# battiny_power_module.net
KiCad netlist of a schematic drawn in EAGLE
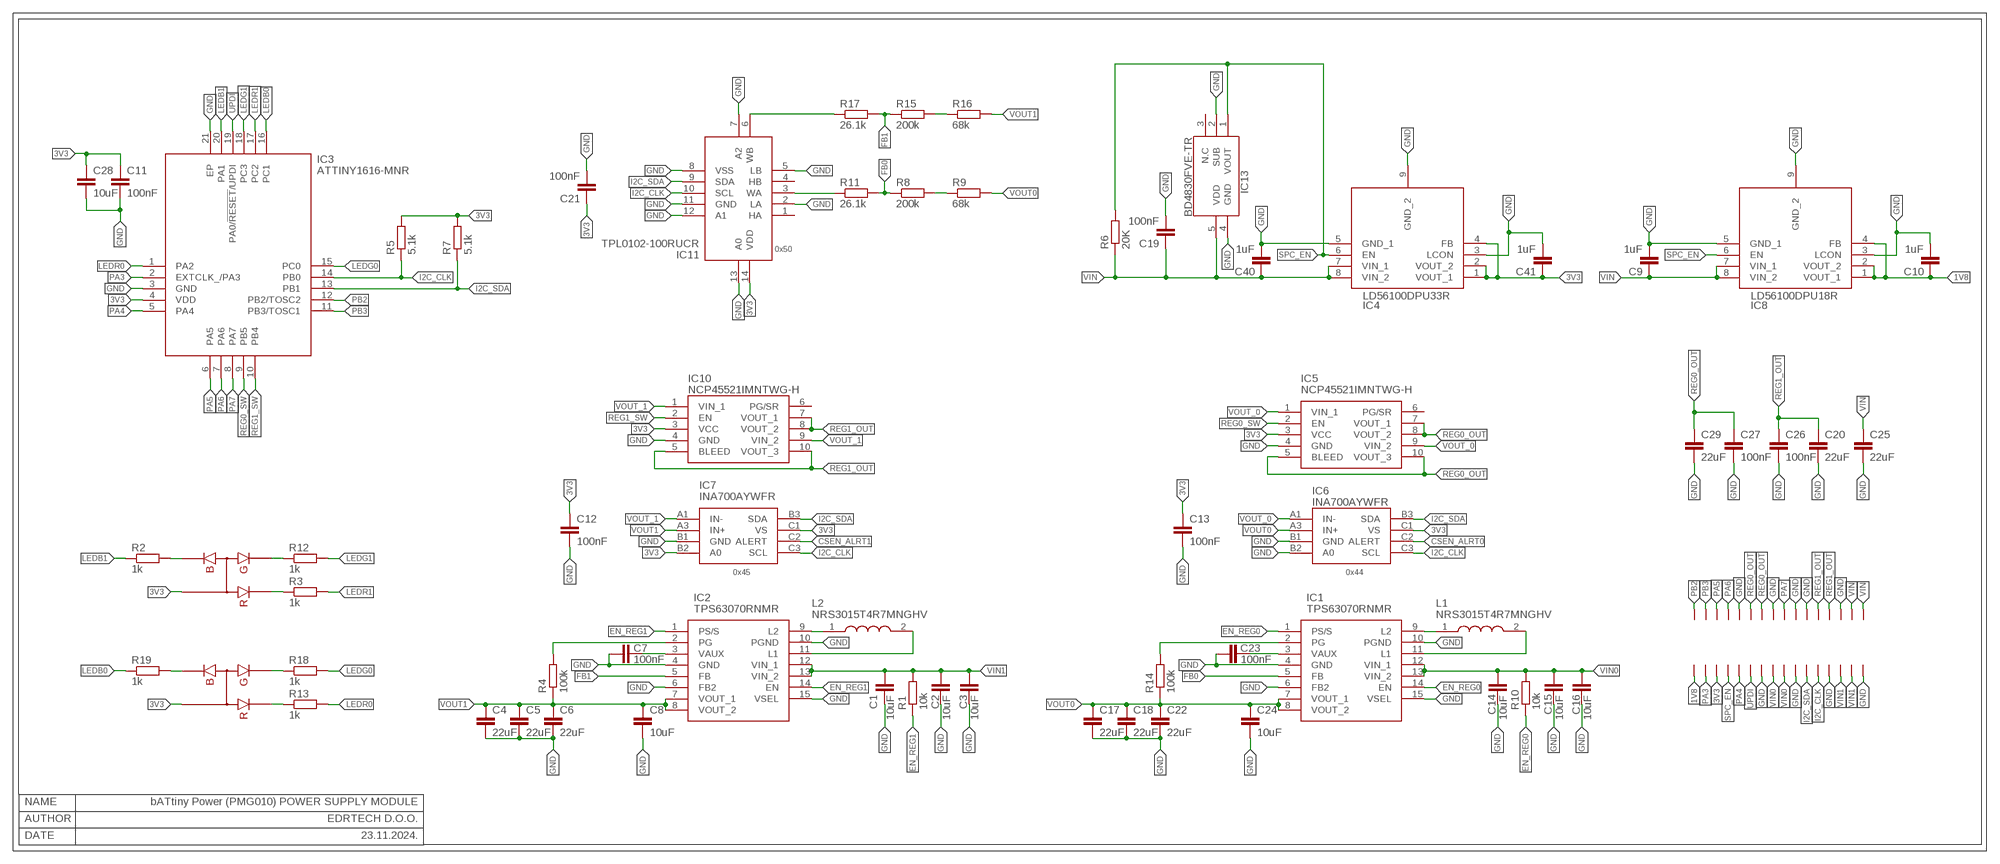
[diagram p0: schematic, sheet 1]

(export (version "E")
  (design (tool "Eeschema 10.0.6"))
  (components
    (comp (ref "C1")
      (value "10uF")
      (footprint "eagle-import:C0402")
      (libsource (lib "eagle-import") (part "C-EUC0402"))
    )
    (comp (ref "C2")
      (value "10uF")
      (footprint "eagle-import:C0402")
      (libsource (lib "eagle-import") (part "C-EUC0402"))
    )
    (comp (ref "C3")
      (value "10uF")
      (footprint "eagle-import:C0402")
      (libsource (lib "eagle-import") (part "C-EUC0402"))
    )
    (comp (ref "C4")
      (value "22uF")
      (footprint "eagle-import:C0603")
      (libsource (lib "eagle-import") (part "C-EUC0603"))
    )
    (comp (ref "C5")
      (value "22uF")
      (footprint "eagle-import:C0603")
      (libsource (lib "eagle-import") (part "C-EUC0603"))
    )
    (comp (ref "C6")
      (value "22uF")
      (footprint "eagle-import:C0603")
      (libsource (lib "eagle-import") (part "C-EUC0603"))
    )
    (comp (ref "C7")
      (value "100nF")
      (footprint "eagle-import:HPC0201")
      (libsource (lib "eagle-import") (part "C-EUHPC0201"))
    )
    (comp (ref "C8")
      (value "10uF")
      (footprint "eagle-import:C0402")
      (libsource (lib "eagle-import") (part "C-EUC0402"))
    )
    (comp (ref "C9")
      (value "1uF")
      (footprint "eagle-import:C0201")
      (libsource (lib "eagle-import") (part "C-EUC0201"))
    )
    (comp (ref "C10")
      (value "1uF")
      (footprint "eagle-import:C0201")
      (libsource (lib "eagle-import") (part "C-EUC0201"))
    )
    (comp (ref "C11")
      (value "100nF")
      (footprint "eagle-import:C0201")
      (libsource (lib "eagle-import") (part "C-EUC0201"))
    )
    (comp (ref "C12")
      (value "100nF")
      (footprint "eagle-import:C0201")
      (libsource (lib "eagle-import") (part "C-EUC0201"))
    )
    (comp (ref "C13")
      (value "100nF")
      (footprint "eagle-import:C0201")
      (libsource (lib "eagle-import") (part "C-EUC0201"))
    )
    (comp (ref "C14")
      (value "10uF")
      (footprint "eagle-import:C0402")
      (libsource (lib "eagle-import") (part "C-EUC0402"))
    )
    (comp (ref "C15")
      (value "10uF")
      (footprint "eagle-import:C0402")
      (libsource (lib "eagle-import") (part "C-EUC0402"))
    )
    (comp (ref "C16")
      (value "10uF")
      (footprint "eagle-import:C0402")
      (libsource (lib "eagle-import") (part "C-EUC0402"))
    )
    (comp (ref "C17")
      (value "22uF")
      (footprint "eagle-import:C0603")
      (libsource (lib "eagle-import") (part "C-EUC0603"))
    )
    (comp (ref "C18")
      (value "22uF")
      (footprint "eagle-import:C0603")
      (libsource (lib "eagle-import") (part "C-EUC0603"))
    )
    (comp (ref "C19")
      (value "100nF")
      (footprint "eagle-import:C0201")
      (libsource (lib "eagle-import") (part "C-EUC0201"))
    )
    (comp (ref "C20")
      (value "22uF")
      (footprint "eagle-import:C0805K")
      (libsource (lib "eagle-import") (part "C-EUC0805K"))
    )
    (comp (ref "C21")
      (value "100nF")
      (footprint "eagle-import:C0201")
      (libsource (lib "eagle-import") (part "C-EUC0201"))
    )
    (comp (ref "C22")
      (value "22uF")
      (footprint "eagle-import:C0603")
      (libsource (lib "eagle-import") (part "C-EUC0603"))
    )
    (comp (ref "C23")
      (value "100nF")
      (footprint "eagle-import:HPC0201")
      (libsource (lib "eagle-import") (part "C-EUHPC0201"))
    )
    (comp (ref "C24")
      (value "10uF")
      (footprint "eagle-import:C0402")
      (libsource (lib "eagle-import") (part "C-EUC0402"))
    )
    (comp (ref "C25")
      (value "22uF")
      (footprint "eagle-import:C0805K")
      (libsource (lib "eagle-import") (part "C-EUC0805K"))
    )
    (comp (ref "C26")
      (value "100nF")
      (footprint "eagle-import:C0603")
      (libsource (lib "eagle-import") (part "C-EUC0603"))
    )
    (comp (ref "C27")
      (value "100nF")
      (footprint "eagle-import:C0603")
      (libsource (lib "eagle-import") (part "C-EUC0603"))
    )
    (comp (ref "C28")
      (value "10uF")
      (footprint "eagle-import:C0402")
      (libsource (lib "eagle-import") (part "C-EUC0402"))
    )
    (comp (ref "C29")
      (value "22uF")
      (footprint "eagle-import:C0805K")
      (libsource (lib "eagle-import") (part "C-EUC0805K"))
    )
    (comp (ref "C40")
      (value "1uF")
      (footprint "eagle-import:C0201")
      (libsource (lib "eagle-import") (part "C-EUC0201"))
    )
    (comp (ref "C41")
      (value "1uF")
      (footprint "eagle-import:C0201")
      (libsource (lib "eagle-import") (part "C-EUC0201"))
    )
    (comp (ref "IC1")
      (value "TPS63070RNMR")
      (footprint "eagle-import:TPS630701RNMR")
      (fields (field (name "MOUSER_PART_NUMBER") "595-TPS63070RNMR"))
      (libsource (lib "eagle-import") (part "TPS63070RNMR"))
    )
    (comp (ref "IC2")
      (value "TPS63070RNMR")
      (footprint "eagle-import:TPS630701RNMR")
      (fields (field (name "MOUSER_PART_NUMBER") "595-TPS63070RNMR"))
      (libsource (lib "eagle-import") (part "TPS63070RNMR"))
    )
    (comp (ref "IC3")
      (value "ATTINY1616-MNR")
      (footprint "eagle-import:QFN40P300X300X90-21N")
      (fields (field (name "MOUSER_PART_NUMBER") "556-ATTINY1616MNR"))
      (libsource (lib "eagle-import") (part "ATTINY1616-MNR"))
    )
    (comp (ref "IC4")
      (value "LD56100DPU30R")
      (footprint "eagle-import:SON40P120X160X50-9N")
      (fields (field (name "MOUSER_PART_NUMBER") "511-LD56100DPU30R"))
      (libsource (lib "eagle-import") (part "LD56100DPU30R"))
    )
    (comp (ref "IC5")
      (value "NCP45521IMNTWG-H")
      (footprint "eagle-import:NCP45521")
      (fields (field (name "MOUSER_PART_NUMBER") "863-NCP45521IMNTWG-H"))
      (libsource (lib "eagle-import") (part "NCP45521IMNTWG-H"))
    )
    (comp (ref "IC6")
      (value "INA700AYWFR")
      (footprint "eagle-import:INA700AYWFR")
      (libsource (lib "eagle-import") (part "INA700AYWFR"))
    )
    (comp (ref "IC7")
      (value "INA700AYWFR")
      (footprint "eagle-import:INA700AYWFR")
      (libsource (lib "eagle-import") (part "INA700AYWFR"))
    )
    (comp (ref "IC8")
      (value "LD56100DPU30R")
      (footprint "eagle-import:SON40P120X160X50-9N")
      (fields (field (name "MOUSER_PART_NUMBER") "511-LD56100DPU30R"))
      (libsource (lib "eagle-import") (part "LD56100DPU30R"))
    )
    (comp (ref "IC10")
      (value "NCP45521IMNTWG-H")
      (footprint "eagle-import:NCP45521")
      (fields (field (name "MOUSER_PART_NUMBER") "863-NCP45521IMNTWG-H"))
      (libsource (lib "eagle-import") (part "NCP45521IMNTWG-H"))
    )
    (comp (ref "IC11")
      (value "TPL0102-100RUCR")
      (footprint "eagle-import:QFN40P200X200X40-14N")
      (libsource (lib "eagle-import") (part "TPL0102-100RUCR"))
    )
    (comp (ref "IC13")
      (value "BD4830FVE-TR")
      (footprint "eagle-import:SOTFL50P160X60-5N")
      (fields (field (name "MOUSER_PART_NUMBER") "755-BD4830FVE-TR"))
      (libsource (lib "eagle-import") (part "BD4830FVE-TR"))
    )
    (comp (ref "L1")
      (value "NRS3015T4R7MNGHV")
      (footprint "eagle-import:NRS3015T4R7MNGHV")
      (fields (field (name "MOUSER_PART_NUMBER") "963-NRS3015T4R7MNGHV"))
      (libsource (lib "eagle-import") (part "NRS3015T4R7MNGHV"))
    )
    (comp (ref "L2")
      (value "NRS3015T4R7MNGHV")
      (footprint "eagle-import:NRS3015T4R7MNGHV")
      (fields (field (name "MOUSER_PART_NUMBER") "963-NRS3015T4R7MNGHV"))
      (libsource (lib "eagle-import") (part "NRS3015T4R7MNGHV"))
    )
    (comp (ref "R1")
      (value "10k")
      (footprint "eagle-import:R0201")
      (libsource (lib "eagle-import") (part "R-EU_R0201"))
    )
    (comp (ref "R2")
      (value "1k")
      (footprint "eagle-import:R0201")
      (libsource (lib "eagle-import") (part "R-EU_R0201"))
    )
    (comp (ref "R3")
      (value "1k")
      (footprint "eagle-import:R0201")
      (libsource (lib "eagle-import") (part "R-EU_R0201"))
    )
    (comp (ref "R4")
      (value "100k")
      (footprint "eagle-import:R0201")
      (libsource (lib "eagle-import") (part "R-EU_R0201"))
    )
    (comp (ref "R5")
      (value "5.1k")
      (footprint "eagle-import:R0201")
      (libsource (lib "eagle-import") (part "R-EU_R0201"))
    )
    (comp (ref "R6")
      (value "20K")
      (footprint "eagle-import:R0201")
      (libsource (lib "eagle-import") (part "R-EU_R0201"))
    )
    (comp (ref "R7")
      (value "5.1k")
      (footprint "eagle-import:R0201")
      (libsource (lib "eagle-import") (part "R-EU_R0201"))
    )
    (comp (ref "R8")
      (value "200k")
      (footprint "eagle-import:R0201")
      (libsource (lib "eagle-import") (part "R-EU_R0201"))
    )
    (comp (ref "R9")
      (value "68k")
      (footprint "eagle-import:R0201")
      (libsource (lib "eagle-import") (part "R-EU_R0201"))
    )
    (comp (ref "R10")
      (value "10k")
      (footprint "eagle-import:R0201")
      (libsource (lib "eagle-import") (part "R-EU_R0201"))
    )
    (comp (ref "R11")
      (value "26.1k")
      (footprint "eagle-import:R0201")
      (libsource (lib "eagle-import") (part "R-EU_R0201"))
    )
    (comp (ref "R12")
      (value "1k")
      (footprint "eagle-import:R0201")
      (libsource (lib "eagle-import") (part "R-EU_R0201"))
    )
    (comp (ref "R13")
      (value "1k")
      (footprint "eagle-import:R0201")
      (libsource (lib "eagle-import") (part "R-EU_R0201"))
    )
    (comp (ref "R14")
      (value "100k")
      (footprint "eagle-import:R0201")
      (libsource (lib "eagle-import") (part "R-EU_R0201"))
    )
    (comp (ref "R15")
      (value "200k")
      (footprint "eagle-import:R0201")
      (libsource (lib "eagle-import") (part "R-EU_R0201"))
    )
    (comp (ref "R16")
      (value "68k")
      (footprint "eagle-import:R0201")
      (libsource (lib "eagle-import") (part "R-EU_R0201"))
    )
    (comp (ref "R17")
      (value "26.1k")
      (footprint "eagle-import:R0201")
      (libsource (lib "eagle-import") (part "R-EU_R0201"))
    )
    (comp (ref "R18")
      (value "1k")
      (footprint "eagle-import:R0201")
      (libsource (lib "eagle-import") (part "R-EU_R0201"))
    )
    (comp (ref "R19")
      (value "1k")
      (footprint "eagle-import:R0201")
      (libsource (lib "eagle-import") (part "R-EU_R0201"))
    )
    (comp (ref "U$1")
      (value "1.27_CH_16P")
      (footprint "eagle-import:1.27_CH_16P")
      (libsource (lib "eagle-import") (part "1.27_CH_16P"))
    )
    (comp (ref "U$2")
      (value "1.27_CH_16P")
      (footprint "eagle-import:1.27_CH_16P")
      (libsource (lib "eagle-import") (part "1.27_CH_16P"))
    )
    (comp (ref "U$3")
      (value "XL-B1010RGBT-HF")
      (footprint "eagle-import:TBA-C1010MB-J2I16")
      (libsource (lib "eagle-import") (part "XL-B1010RGBT-HF"))
    )
    (comp (ref "U$4")
      (value "XL-B1010RGBT-HF")
      (footprint "eagle-import:TBA-C1010MB-J2I16")
      (libsource (lib "eagle-import") (part "XL-B1010RGBT-HF"))
    )
  )
  (nets
    (net (code "1") (name "1V8") (class "Default")
      (node (ref "C10") (pin "1") (pinfunction "1_1") (pintype "passive"))
      (node (ref "IC8") (pin "1") (pinfunction "VOUT_1_1") (pintype "bidirectional"))
      (node (ref "IC8") (pin "2") (pinfunction "VOUT_2_2") (pintype "bidirectional"))
      (node (ref "IC8") (pin "4") (pinfunction "FB_4") (pintype "bidirectional"))
      (node (ref "U$2") (pin "P$32") (pinfunction "P$16_P$32") (pintype "bidirectional"))
      (node (ref "U$2") (pin "P$48") (pinfunction "P$16_P$48") (pintype "bidirectional"))
    )
    (net (code "2") (name "3V3") (class "Default")
      (node (ref "C11") (pin "1") (pinfunction "1_1") (pintype "passive"))
      (node (ref "C12") (pin "1") (pinfunction "1_1") (pintype "passive"))
      (node (ref "C13") (pin "1") (pinfunction "1_1") (pintype "passive"))
      (node (ref "C21") (pin "1") (pinfunction "1_1") (pintype "passive"))
      (node (ref "C28") (pin "1") (pinfunction "1_1") (pintype "passive"))
      (node (ref "C41") (pin "1") (pinfunction "1_1") (pintype "passive"))
      (node (ref "IC10") (pin "3") (pinfunction "VCC_3") (pintype "bidirectional"))
      (node (ref "IC11") (pin "14") (pinfunction "VDD_14") (pintype "bidirectional"))
      (node (ref "IC3") (pin "4") (pinfunction "VDD_4") (pintype "bidirectional"))
      (node (ref "IC4") (pin "1") (pinfunction "VOUT_1_1") (pintype "bidirectional"))
      (node (ref "IC4") (pin "2") (pinfunction "VOUT_2_2") (pintype "bidirectional"))
      (node (ref "IC4") (pin "4") (pinfunction "FB_4") (pintype "bidirectional"))
      (node (ref "IC5") (pin "3") (pinfunction "VCC_3") (pintype "bidirectional"))
      (node (ref "IC6") (pin "C1") (pinfunction "VS_C1") (pintype "bidirectional"))
      (node (ref "IC7") (pin "B2") (pinfunction "A0_B2") (pintype "bidirectional"))
      (node (ref "IC7") (pin "C1") (pinfunction "VS_C1") (pintype "bidirectional"))
      (node (ref "R5") (pin "2") (pinfunction "2_2") (pintype "passive"))
      (node (ref "R7") (pin "2") (pinfunction "2_2") (pintype "passive"))
      (node (ref "U$2") (pin "P$30") (pinfunction "P$14_P$30") (pintype "bidirectional"))
      (node (ref "U$2") (pin "P$46") (pinfunction "P$14_P$46") (pintype "bidirectional"))
      (node (ref "U$3") (pin "P$3") (pinfunction "P$2_P$3") (pintype "bidirectional"))
      (node (ref "U$4") (pin "P$3") (pinfunction "P$2_P$3") (pintype "bidirectional"))
    )
    (net (code "3") (name "CSEN_ALRT0") (class "Default")
      (node (ref "IC6") (pin "C2") (pinfunction "ALERT_C2") (pintype "bidirectional"))
    )
    (net (code "4") (name "CSEN_ALRT1") (class "Default")
      (node (ref "IC7") (pin "C2") (pinfunction "ALERT_C2") (pintype "bidirectional"))
    )
    (net (code "5") (name "EN_REG0") (class "Default")
      (node (ref "IC1") (pin "1") (pinfunction "PS/S_1") (pintype "bidirectional"))
      (node (ref "IC1") (pin "14") (pinfunction "EN_14") (pintype "bidirectional"))
      (node (ref "R10") (pin "1") (pinfunction "1_1") (pintype "passive"))
    )
    (net (code "6") (name "EN_REG1") (class "Default")
      (node (ref "IC2") (pin "1") (pinfunction "PS/S_1") (pintype "bidirectional"))
      (node (ref "IC2") (pin "14") (pinfunction "EN_14") (pintype "bidirectional"))
      (node (ref "R1") (pin "1") (pinfunction "1_1") (pintype "passive"))
    )
    (net (code "7") (name "FB0") (class "Default")
      (node (ref "IC1") (pin "5") (pinfunction "FB_5") (pintype "bidirectional"))
      (node (ref "R11") (pin "2") (pinfunction "2_2") (pintype "passive"))
      (node (ref "R8") (pin "1") (pinfunction "1_1") (pintype "passive"))
    )
    (net (code "8") (name "FB1") (class "Default")
      (node (ref "IC2") (pin "5") (pinfunction "FB_5") (pintype "bidirectional"))
      (node (ref "R15") (pin "1") (pinfunction "1_1") (pintype "passive"))
      (node (ref "R17") (pin "2") (pinfunction "2_2") (pintype "passive"))
    )
    (net (code "9") (name "GND") (class "Default")
      (node (ref "C1") (pin "2") (pinfunction "2_2") (pintype "passive"))
      (node (ref "C10") (pin "2") (pinfunction "2_2") (pintype "passive"))
      (node (ref "C11") (pin "2") (pinfunction "2_2") (pintype "passive"))
      (node (ref "C12") (pin "2") (pinfunction "2_2") (pintype "passive"))
      (node (ref "C13") (pin "2") (pinfunction "2_2") (pintype "passive"))
      (node (ref "C14") (pin "2") (pinfunction "2_2") (pintype "passive"))
      (node (ref "C15") (pin "2") (pinfunction "2_2") (pintype "passive"))
      (node (ref "C16") (pin "2") (pinfunction "2_2") (pintype "passive"))
      (node (ref "C17") (pin "2") (pinfunction "2_2") (pintype "passive"))
      (node (ref "C18") (pin "2") (pinfunction "2_2") (pintype "passive"))
      (node (ref "C19") (pin "2") (pinfunction "2_2") (pintype "passive"))
      (node (ref "C2") (pin "2") (pinfunction "2_2") (pintype "passive"))
      (node (ref "C20") (pin "2") (pinfunction "2_2") (pintype "passive"))
      (node (ref "C21") (pin "2") (pinfunction "2_2") (pintype "passive"))
      (node (ref "C22") (pin "2") (pinfunction "2_2") (pintype "passive"))
      (node (ref "C23") (pin "1") (pinfunction "1_1") (pintype "passive"))
      (node (ref "C24") (pin "2") (pinfunction "2_2") (pintype "passive"))
      (node (ref "C25") (pin "2") (pinfunction "2_2") (pintype "passive"))
      (node (ref "C26") (pin "2") (pinfunction "2_2") (pintype "passive"))
      (node (ref "C27") (pin "2") (pinfunction "2_2") (pintype "passive"))
      (node (ref "C28") (pin "2") (pinfunction "2_2") (pintype "passive"))
      (node (ref "C29") (pin "2") (pinfunction "2_2") (pintype "passive"))
      (node (ref "C3") (pin "2") (pinfunction "2_2") (pintype "passive"))
      (node (ref "C4") (pin "2") (pinfunction "2_2") (pintype "passive"))
      (node (ref "C40") (pin "2") (pinfunction "2_2") (pintype "passive"))
      (node (ref "C41") (pin "2") (pinfunction "2_2") (pintype "passive"))
      (node (ref "C5") (pin "2") (pinfunction "2_2") (pintype "passive"))
      (node (ref "C6") (pin "2") (pinfunction "2_2") (pintype "passive"))
      (node (ref "C7") (pin "1") (pinfunction "1_1") (pintype "passive"))
      (node (ref "C8") (pin "2") (pinfunction "2_2") (pintype "passive"))
      (node (ref "C9") (pin "2") (pinfunction "2_2") (pintype "passive"))
      (node (ref "IC1") (pin "10") (pinfunction "PGND_10") (pintype "bidirectional"))
      (node (ref "IC1") (pin "15") (pinfunction "VSEL_15") (pintype "bidirectional"))
      (node (ref "IC1") (pin "4") (pinfunction "GND_4") (pintype "bidirectional"))
      (node (ref "IC1") (pin "6") (pinfunction "FB2_6") (pintype "bidirectional"))
      (node (ref "IC10") (pin "4") (pinfunction "GND_4") (pintype "bidirectional"))
      (node (ref "IC11") (pin "11") (pinfunction "GND_11") (pintype "bidirectional"))
      (node (ref "IC11") (pin "12") (pinfunction "A1_12") (pintype "bidirectional"))
      (node (ref "IC11") (pin "13") (pinfunction "A0_13") (pintype "bidirectional"))
      (node (ref "IC11") (pin "2") (pinfunction "LA_2") (pintype "bidirectional"))
      (node (ref "IC11") (pin "5") (pinfunction "LB_5") (pintype "bidirectional"))
      (node (ref "IC11") (pin "7") (pinfunction "A2_7") (pintype "bidirectional"))
      (node (ref "IC11") (pin "8") (pinfunction "VSS_8") (pintype "bidirectional"))
      (node (ref "IC13") (pin "2") (pinfunction "SUB_2") (pintype "bidirectional"))
      (node (ref "IC13") (pin "4") (pinfunction "GND_4") (pintype "bidirectional"))
      (node (ref "IC2") (pin "10") (pinfunction "PGND_10") (pintype "bidirectional"))
      (node (ref "IC2") (pin "15") (pinfunction "VSEL_15") (pintype "bidirectional"))
      (node (ref "IC2") (pin "4") (pinfunction "GND_4") (pintype "bidirectional"))
      (node (ref "IC2") (pin "6") (pinfunction "FB2_6") (pintype "bidirectional"))
      (node (ref "IC3") (pin "21") (pinfunction "EP_21") (pintype "bidirectional"))
      (node (ref "IC3") (pin "3") (pinfunction "GND_3") (pintype "bidirectional"))
      (node (ref "IC4") (pin "3") (pinfunction "LCON_3") (pintype "bidirectional"))
      (node (ref "IC4") (pin "5") (pinfunction "GND_1_5") (pintype "bidirectional"))
      (node (ref "IC4") (pin "9") (pinfunction "GND_2_9") (pintype "bidirectional"))
      (node (ref "IC5") (pin "4") (pinfunction "GND_4") (pintype "bidirectional"))
      (node (ref "IC6") (pin "B1") (pinfunction "GND_B1") (pintype "bidirectional"))
      (node (ref "IC6") (pin "B2") (pinfunction "A0_B2") (pintype "bidirectional"))
      (node (ref "IC7") (pin "B1") (pinfunction "GND_B1") (pintype "bidirectional"))
      (node (ref "IC8") (pin "3") (pinfunction "LCON_3") (pintype "bidirectional"))
      (node (ref "IC8") (pin "5") (pinfunction "GND_1_5") (pintype "bidirectional"))
      (node (ref "IC8") (pin "9") (pinfunction "GND_2_9") (pintype "bidirectional"))
      (node (ref "U$1") (pin "P$21") (pinfunction "P$5_P$21") (pintype "bidirectional"))
      (node (ref "U$1") (pin "P$24") (pinfunction "P$8_P$24") (pintype "bidirectional"))
      (node (ref "U$1") (pin "P$26") (pinfunction "P$10_P$26") (pintype "bidirectional"))
      (node (ref "U$1") (pin "P$27") (pinfunction "P$11_P$27") (pintype "bidirectional"))
      (node (ref "U$1") (pin "P$30") (pinfunction "P$14_P$30") (pintype "bidirectional"))
      (node (ref "U$1") (pin "P$37") (pinfunction "P$5_P$37") (pintype "bidirectional"))
      (node (ref "U$1") (pin "P$40") (pinfunction "P$8_P$40") (pintype "bidirectional"))
      (node (ref "U$1") (pin "P$42") (pinfunction "P$10_P$42") (pintype "bidirectional"))
      (node (ref "U$1") (pin "P$43") (pinfunction "P$11_P$43") (pintype "bidirectional"))
      (node (ref "U$1") (pin "P$46") (pinfunction "P$14_P$46") (pintype "bidirectional"))
      (node (ref "U$2") (pin "P$17") (pinfunction "P$1_P$17") (pintype "bidirectional"))
      (node (ref "U$2") (pin "P$20") (pinfunction "P$4_P$20") (pintype "bidirectional"))
      (node (ref "U$2") (pin "P$23") (pinfunction "P$7_P$23") (pintype "bidirectional"))
      (node (ref "U$2") (pin "P$26") (pinfunction "P$10_P$26") (pintype "bidirectional"))
      (node (ref "U$2") (pin "P$33") (pinfunction "P$1_P$33") (pintype "bidirectional"))
      (node (ref "U$2") (pin "P$36") (pinfunction "P$4_P$36") (pintype "bidirectional"))
      (node (ref "U$2") (pin "P$39") (pinfunction "P$7_P$39") (pintype "bidirectional"))
      (node (ref "U$2") (pin "P$42") (pinfunction "P$10_P$42") (pintype "bidirectional"))
    )
    (net (code "10") (name "I2C_CLK") (class "Default")
      (node (ref "IC11") (pin "10") (pinfunction "SCL_10") (pintype "bidirectional"))
      (node (ref "IC3") (pin "14") (pinfunction "PB0_14") (pintype "bidirectional"))
      (node (ref "IC6") (pin "C3") (pinfunction "SCL_C3") (pintype "bidirectional"))
      (node (ref "IC7") (pin "C3") (pinfunction "SCL_C3") (pintype "bidirectional"))
      (node (ref "R5") (pin "1") (pinfunction "1_1") (pintype "passive"))
      (node (ref "U$2") (pin "P$21") (pinfunction "P$5_P$21") (pintype "bidirectional"))
      (node (ref "U$2") (pin "P$37") (pinfunction "P$5_P$37") (pintype "bidirectional"))
    )
    (net (code "11") (name "I2C_SDA") (class "Default")
      (node (ref "IC11") (pin "9") (pinfunction "SDA_9") (pintype "bidirectional"))
      (node (ref "IC3") (pin "13") (pinfunction "PB1_13") (pintype "bidirectional"))
      (node (ref "IC6") (pin "B3") (pinfunction "SDA_B3") (pintype "bidirectional"))
      (node (ref "IC7") (pin "B3") (pinfunction "SDA_B3") (pintype "bidirectional"))
      (node (ref "R7") (pin "1") (pinfunction "1_1") (pintype "passive"))
      (node (ref "U$2") (pin "P$22") (pinfunction "P$6_P$22") (pintype "bidirectional"))
      (node (ref "U$2") (pin "P$38") (pinfunction "P$6_P$38") (pintype "bidirectional"))
    )
    (net (code "12") (name "LEDB0") (class "Default")
      (node (ref "IC3") (pin "16") (pinfunction "PC1_16") (pintype "bidirectional"))
      (node (ref "R19") (pin "1") (pinfunction "1_1") (pintype "passive"))
    )
    (net (code "13") (name "LEDB1") (class "Default")
      (node (ref "IC3") (pin "20") (pinfunction "PA1_20") (pintype "bidirectional"))
      (node (ref "R2") (pin "1") (pinfunction "1_1") (pintype "passive"))
    )
    (net (code "14") (name "LEDG0") (class "Default")
      (node (ref "IC3") (pin "15") (pinfunction "PC0_15") (pintype "bidirectional"))
      (node (ref "R18") (pin "2") (pinfunction "2_2") (pintype "passive"))
    )
    (net (code "15") (name "LEDG1") (class "Default")
      (node (ref "IC3") (pin "18") (pinfunction "PC3_18") (pintype "bidirectional"))
      (node (ref "R12") (pin "2") (pinfunction "2_2") (pintype "passive"))
    )
    (net (code "16") (name "LEDR0") (class "Default")
      (node (ref "IC3") (pin "1") (pinfunction "PA2_1") (pintype "bidirectional"))
      (node (ref "R13") (pin "2") (pinfunction "2_2") (pintype "passive"))
    )
    (net (code "17") (name "LEDR1") (class "Default")
      (node (ref "IC3") (pin "17") (pinfunction "PC2_17") (pintype "bidirectional"))
      (node (ref "R3") (pin "2") (pinfunction "2_2") (pintype "passive"))
    )
    (net (code "18") (name "Net-(IC1-L1)") (class "Default")
      (node (ref "IC1") (pin "11") (pinfunction "L1_11") (pintype "bidirectional"))
      (node (ref "L1") (pin "2") (pinfunction "2_2") (pintype "bidirectional"))
    )
    (net (code "19") (name "Net-(IC1-L2)") (class "Default")
      (node (ref "IC1") (pin "9") (pinfunction "L2_9") (pintype "bidirectional"))
      (node (ref "L1") (pin "1") (pinfunction "1_1") (pintype "bidirectional"))
    )
    (net (code "20") (name "Net-(IC1-PG)") (class "Default")
      (node (ref "IC1") (pin "2") (pinfunction "PG_2") (pintype "bidirectional"))
      (node (ref "R14") (pin "2") (pinfunction "2_2") (pintype "passive"))
    )
    (net (code "21") (name "Net-(IC1-VAUX)") (class "Default")
      (node (ref "C23") (pin "2") (pinfunction "2_2") (pintype "passive"))
      (node (ref "IC1") (pin "3") (pinfunction "VAUX_3") (pintype "bidirectional"))
    )
    (net (code "22") (name "Net-(IC2-L1)") (class "Default")
      (node (ref "IC2") (pin "11") (pinfunction "L1_11") (pintype "bidirectional"))
      (node (ref "L2") (pin "2") (pinfunction "2_2") (pintype "bidirectional"))
    )
    (net (code "23") (name "Net-(IC2-L2)") (class "Default")
      (node (ref "IC2") (pin "9") (pinfunction "L2_9") (pintype "bidirectional"))
      (node (ref "L2") (pin "1") (pinfunction "1_1") (pintype "bidirectional"))
    )
    (net (code "24") (name "Net-(IC2-PG)") (class "Default")
      (node (ref "IC2") (pin "2") (pinfunction "PG_2") (pintype "bidirectional"))
      (node (ref "R4") (pin "2") (pinfunction "2_2") (pintype "passive"))
    )
    (net (code "25") (name "Net-(IC2-VAUX)") (class "Default")
      (node (ref "C7") (pin "2") (pinfunction "2_2") (pintype "passive"))
      (node (ref "IC2") (pin "3") (pinfunction "VAUX_3") (pintype "bidirectional"))
    )
    (net (code "26") (name "Net-(IC11-WA)") (class "Default")
      (node (ref "IC11") (pin "3") (pinfunction "WA_3") (pintype "bidirectional"))
      (node (ref "R11") (pin "1") (pinfunction "1_1") (pintype "passive"))
    )
    (net (code "27") (name "Net-(IC11-WB)") (class "Default")
      (node (ref "IC11") (pin "6") (pinfunction "WB_6") (pintype "bidirectional"))
      (node (ref "R17") (pin "1") (pinfunction "1_1") (pintype "passive"))
    )
    (net (code "28") (name "Net-(R8-Pad2)") (class "Default")
      (node (ref "R8") (pin "2") (pinfunction "2_2") (pintype "passive"))
      (node (ref "R9") (pin "1") (pinfunction "1_1") (pintype "passive"))
    )
    (net (code "29") (name "Net-(R15-Pad2)") (class "Default")
      (node (ref "R15") (pin "2") (pinfunction "2_2") (pintype "passive"))
      (node (ref "R16") (pin "1") (pinfunction "1_1") (pintype "passive"))
    )
    (net (code "30") (name "Net-(U$3-P$1)") (class "Default")
      (node (ref "R13") (pin "1") (pinfunction "1_1") (pintype "passive"))
      (node (ref "U$3") (pin "P$4") (pinfunction "P$1_P$4") (pintype "bidirectional"))
    )
    (net (code "31") (name "Net-(U$3-P$3)") (class "Default")
      (node (ref "R18") (pin "1") (pinfunction "1_1") (pintype "passive"))
      (node (ref "U$3") (pin "P$2") (pinfunction "P$3_P$2") (pintype "bidirectional"))
    )
    (net (code "32") (name "Net-(U$3-P$4)") (class "Default")
      (node (ref "R19") (pin "2") (pinfunction "2_2") (pintype "passive"))
      (node (ref "U$3") (pin "P$1") (pinfunction "P$4_P$1") (pintype "bidirectional"))
    )
    (net (code "33") (name "Net-(U$4-P$1)") (class "Default")
      (node (ref "R3") (pin "1") (pinfunction "1_1") (pintype "passive"))
      (node (ref "U$4") (pin "P$4") (pinfunction "P$1_P$4") (pintype "bidirectional"))
    )
    (net (code "34") (name "Net-(U$4-P$3)") (class "Default")
      (node (ref "R12") (pin "1") (pinfunction "1_1") (pintype "passive"))
      (node (ref "U$4") (pin "P$2") (pinfunction "P$3_P$2") (pintype "bidirectional"))
    )
    (net (code "35") (name "Net-(U$4-P$4)") (class "Default")
      (node (ref "R2") (pin "2") (pinfunction "2_2") (pintype "passive"))
      (node (ref "U$4") (pin "P$1") (pinfunction "P$4_P$1") (pintype "bidirectional"))
    )
    (net (code "36") (name "PA3") (class "Default")
      (node (ref "IC3") (pin "2") (pinfunction "EXTCLK_/PA3_2") (pintype "bidirectional"))
      (node (ref "U$2") (pin "P$31") (pinfunction "P$15_P$31") (pintype "bidirectional"))
      (node (ref "U$2") (pin "P$47") (pinfunction "P$15_P$47") (pintype "bidirectional"))
    )
    (net (code "37") (name "PA4") (class "Default")
      (node (ref "IC3") (pin "5") (pinfunction "PA4_5") (pintype "bidirectional"))
      (node (ref "U$2") (pin "P$28") (pinfunction "P$12_P$28") (pintype "bidirectional"))
      (node (ref "U$2") (pin "P$44") (pinfunction "P$12_P$44") (pintype "bidirectional"))
    )
    (net (code "38") (name "PA5") (class "Default")
      (node (ref "IC3") (pin "6") (pinfunction "PA5_6") (pintype "bidirectional"))
      (node (ref "U$1") (pin "P$19") (pinfunction "P$3_P$19") (pintype "bidirectional"))
      (node (ref "U$1") (pin "P$35") (pinfunction "P$3_P$35") (pintype "bidirectional"))
    )
    (net (code "39") (name "PA6") (class "Default")
      (node (ref "IC3") (pin "7") (pinfunction "PA6_7") (pintype "bidirectional"))
      (node (ref "U$1") (pin "P$20") (pinfunction "P$4_P$20") (pintype "bidirectional"))
      (node (ref "U$1") (pin "P$36") (pinfunction "P$4_P$36") (pintype "bidirectional"))
    )
    (net (code "40") (name "PA7") (class "Default")
      (node (ref "IC3") (pin "8") (pinfunction "PA7_8") (pintype "bidirectional"))
      (node (ref "U$1") (pin "P$25") (pinfunction "P$9_P$25") (pintype "bidirectional"))
      (node (ref "U$1") (pin "P$41") (pinfunction "P$9_P$41") (pintype "bidirectional"))
    )
    (net (code "41") (name "PB2") (class "Default")
      (node (ref "IC3") (pin "12") (pinfunction "PB2/TOSC2_12") (pintype "bidirectional"))
      (node (ref "U$1") (pin "P$17") (pinfunction "P$1_P$17") (pintype "bidirectional"))
      (node (ref "U$1") (pin "P$33") (pinfunction "P$1_P$33") (pintype "bidirectional"))
    )
    (net (code "42") (name "PB3") (class "Default")
      (node (ref "IC3") (pin "11") (pinfunction "PB3/TOSC1_11") (pintype "bidirectional"))
      (node (ref "U$1") (pin "P$18") (pinfunction "P$2_P$18") (pintype "bidirectional"))
      (node (ref "U$1") (pin "P$34") (pinfunction "P$2_P$34") (pintype "bidirectional"))
    )
    (net (code "43") (name "REG0_OUT") (class "Default")
      (node (ref "C27") (pin "1") (pinfunction "1_1") (pintype "passive"))
      (node (ref "C29") (pin "1") (pinfunction "1_1") (pintype "passive"))
      (node (ref "IC5") (pin "10") (pinfunction "VOUT_3_10") (pintype "bidirectional"))
      (node (ref "IC5") (pin "5") (pinfunction "BLEED_5") (pintype "bidirectional"))
      (node (ref "IC5") (pin "7") (pinfunction "VOUT_1_7") (pintype "bidirectional"))
      (node (ref "IC5") (pin "8") (pinfunction "VOUT_2_8") (pintype "bidirectional"))
      (node (ref "U$1") (pin "P$22") (pinfunction "P$6_P$22") (pintype "bidirectional"))
      (node (ref "U$1") (pin "P$23") (pinfunction "P$7_P$23") (pintype "bidirectional"))
      (node (ref "U$1") (pin "P$38") (pinfunction "P$6_P$38") (pintype "bidirectional"))
      (node (ref "U$1") (pin "P$39") (pinfunction "P$7_P$39") (pintype "bidirectional"))
    )
    (net (code "44") (name "REG0_SW") (class "Default")
      (node (ref "IC3") (pin "9") (pinfunction "PB5_9") (pintype "bidirectional"))
      (node (ref "IC5") (pin "2") (pinfunction "EN_2") (pintype "bidirectional"))
    )
    (net (code "45") (name "REG1_OUT") (class "Default")
      (node (ref "C20") (pin "1") (pinfunction "1_1") (pintype "passive"))
      (node (ref "C26") (pin "1") (pinfunction "1_1") (pintype "passive"))
      (node (ref "IC10") (pin "10") (pinfunction "VOUT_3_10") (pintype "bidirectional"))
      (node (ref "IC10") (pin "5") (pinfunction "BLEED_5") (pintype "bidirectional"))
      (node (ref "IC10") (pin "7") (pinfunction "VOUT_1_7") (pintype "bidirectional"))
      (node (ref "IC10") (pin "8") (pinfunction "VOUT_2_8") (pintype "bidirectional"))
      (node (ref "U$1") (pin "P$28") (pinfunction "P$12_P$28") (pintype "bidirectional"))
      (node (ref "U$1") (pin "P$29") (pinfunction "P$13_P$29") (pintype "bidirectional"))
      (node (ref "U$1") (pin "P$44") (pinfunction "P$12_P$44") (pintype "bidirectional"))
      (node (ref "U$1") (pin "P$45") (pinfunction "P$13_P$45") (pintype "bidirectional"))
    )
    (net (code "46") (name "REG1_SW") (class "Default")
      (node (ref "IC10") (pin "2") (pinfunction "EN_2") (pintype "bidirectional"))
      (node (ref "IC3") (pin "10") (pinfunction "PB4_10") (pintype "bidirectional"))
    )
    (net (code "47") (name "SPC_EN") (class "Default")
      (node (ref "IC13") (pin "1") (pinfunction "VOUT_1") (pintype "bidirectional"))
      (node (ref "IC4") (pin "6") (pinfunction "EN_6") (pintype "bidirectional"))
      (node (ref "IC8") (pin "6") (pinfunction "EN_6") (pintype "bidirectional"))
      (node (ref "R6") (pin "2") (pinfunction "2_2") (pintype "passive"))
      (node (ref "U$2") (pin "P$29") (pinfunction "P$13_P$29") (pintype "bidirectional"))
      (node (ref "U$2") (pin "P$45") (pinfunction "P$13_P$45") (pintype "bidirectional"))
    )
    (net (code "48") (name "UPDI") (class "Default")
      (node (ref "IC3") (pin "19") (pinfunction "PA0/~{RESET}/UPDI_19") (pintype "bidirectional"))
      (node (ref "U$2") (pin "P$27") (pinfunction "P$11_P$27") (pintype "bidirectional"))
      (node (ref "U$2") (pin "P$43") (pinfunction "P$11_P$43") (pintype "bidirectional"))
    )
    (net (code "49") (name "VIN") (class "Default")
      (node (ref "C19") (pin "1") (pinfunction "1_1") (pintype "passive"))
      (node (ref "C25") (pin "1") (pinfunction "1_1") (pintype "passive"))
      (node (ref "C40") (pin "1") (pinfunction "1_1") (pintype "passive"))
      (node (ref "C9") (pin "1") (pinfunction "1_1") (pintype "passive"))
      (node (ref "IC13") (pin "5") (pinfunction "VDD_5") (pintype "bidirectional"))
      (node (ref "IC4") (pin "7") (pinfunction "VIN_1_7") (pintype "bidirectional"))
      (node (ref "IC4") (pin "8") (pinfunction "VIN_2_8") (pintype "bidirectional"))
      (node (ref "IC8") (pin "7") (pinfunction "VIN_1_7") (pintype "bidirectional"))
      (node (ref "IC8") (pin "8") (pinfunction "VIN_2_8") (pintype "bidirectional"))
      (node (ref "R6") (pin "1") (pinfunction "1_1") (pintype "passive"))
      (node (ref "U$1") (pin "P$31") (pinfunction "P$15_P$31") (pintype "bidirectional"))
      (node (ref "U$1") (pin "P$32") (pinfunction "P$16_P$32") (pintype "bidirectional"))
      (node (ref "U$1") (pin "P$47") (pinfunction "P$15_P$47") (pintype "bidirectional"))
      (node (ref "U$1") (pin "P$48") (pinfunction "P$16_P$48") (pintype "bidirectional"))
    )
    (net (code "50") (name "VIN0") (class "Default")
      (node (ref "C14") (pin "1") (pinfunction "1_1") (pintype "passive"))
      (node (ref "C15") (pin "1") (pinfunction "1_1") (pintype "passive"))
      (node (ref "C16") (pin "1") (pinfunction "1_1") (pintype "passive"))
      (node (ref "IC1") (pin "12") (pinfunction "VIN_1_12") (pintype "bidirectional"))
      (node (ref "IC1") (pin "13") (pinfunction "VIN_2_13") (pintype "bidirectional"))
      (node (ref "R10") (pin "2") (pinfunction "2_2") (pintype "passive"))
      (node (ref "U$2") (pin "P$24") (pinfunction "P$8_P$24") (pintype "bidirectional"))
      (node (ref "U$2") (pin "P$25") (pinfunction "P$9_P$25") (pintype "bidirectional"))
      (node (ref "U$2") (pin "P$40") (pinfunction "P$8_P$40") (pintype "bidirectional"))
      (node (ref "U$2") (pin "P$41") (pinfunction "P$9_P$41") (pintype "bidirectional"))
    )
    (net (code "51") (name "VIN1") (class "Default")
      (node (ref "C1") (pin "1") (pinfunction "1_1") (pintype "passive"))
      (node (ref "C2") (pin "1") (pinfunction "1_1") (pintype "passive"))
      (node (ref "C3") (pin "1") (pinfunction "1_1") (pintype "passive"))
      (node (ref "IC2") (pin "12") (pinfunction "VIN_1_12") (pintype "bidirectional"))
      (node (ref "IC2") (pin "13") (pinfunction "VIN_2_13") (pintype "bidirectional"))
      (node (ref "R1") (pin "2") (pinfunction "2_2") (pintype "passive"))
      (node (ref "U$2") (pin "P$18") (pinfunction "P$2_P$18") (pintype "bidirectional"))
      (node (ref "U$2") (pin "P$19") (pinfunction "P$3_P$19") (pintype "bidirectional"))
      (node (ref "U$2") (pin "P$34") (pinfunction "P$2_P$34") (pintype "bidirectional"))
      (node (ref "U$2") (pin "P$35") (pinfunction "P$3_P$35") (pintype "bidirectional"))
    )
    (net (code "52") (name "VOUT0") (class "Default")
      (node (ref "C17") (pin "1") (pinfunction "1_1") (pintype "passive"))
      (node (ref "C18") (pin "1") (pinfunction "1_1") (pintype "passive"))
      (node (ref "C22") (pin "1") (pinfunction "1_1") (pintype "passive"))
      (node (ref "C24") (pin "1") (pinfunction "1_1") (pintype "passive"))
      (node (ref "IC1") (pin "7") (pinfunction "VOUT_1_7") (pintype "bidirectional"))
      (node (ref "IC1") (pin "8") (pinfunction "VOUT_2_8") (pintype "bidirectional"))
      (node (ref "IC6") (pin "A3") (pinfunction "IN+_A3") (pintype "bidirectional"))
      (node (ref "R14") (pin "1") (pinfunction "1_1") (pintype "passive"))
      (node (ref "R9") (pin "2") (pinfunction "2_2") (pintype "passive"))
    )
    (net (code "53") (name "VOUT1") (class "Default")
      (node (ref "C4") (pin "1") (pinfunction "1_1") (pintype "passive"))
      (node (ref "C5") (pin "1") (pinfunction "1_1") (pintype "passive"))
      (node (ref "C6") (pin "1") (pinfunction "1_1") (pintype "passive"))
      (node (ref "C8") (pin "1") (pinfunction "1_1") (pintype "passive"))
      (node (ref "IC2") (pin "7") (pinfunction "VOUT_1_7") (pintype "bidirectional"))
      (node (ref "IC2") (pin "8") (pinfunction "VOUT_2_8") (pintype "bidirectional"))
      (node (ref "IC7") (pin "A3") (pinfunction "IN+_A3") (pintype "bidirectional"))
      (node (ref "R16") (pin "2") (pinfunction "2_2") (pintype "passive"))
      (node (ref "R4") (pin "1") (pinfunction "1_1") (pintype "passive"))
    )
    (net (code "54") (name "VOUT_0") (class "Default")
      (node (ref "IC5") (pin "1") (pinfunction "VIN_1_1") (pintype "bidirectional"))
      (node (ref "IC5") (pin "9") (pinfunction "VIN_2_9") (pintype "bidirectional"))
      (node (ref "IC6") (pin "A1") (pinfunction "IN-_A1") (pintype "bidirectional"))
    )
    (net (code "55") (name "VOUT_1") (class "Default")
      (node (ref "IC10") (pin "1") (pinfunction "VIN_1_1") (pintype "bidirectional"))
      (node (ref "IC10") (pin "9") (pinfunction "VIN_2_9") (pintype "bidirectional"))
      (node (ref "IC7") (pin "A1") (pinfunction "IN-_A1") (pintype "bidirectional"))
    )
    (net (code "56") (name "unconnected-(IC5-PG{slash}SR-Pad6)") (class "Default")
      (node (ref "IC5") (pin "6") (pinfunction "PG/SR_6") (pintype "bidirectional"))
    )
    (net (code "57") (name "unconnected-(IC10-PG{slash}SR-Pad6)") (class "Default")
      (node (ref "IC10") (pin "6") (pinfunction "PG/SR_6") (pintype "bidirectional"))
    )
    (net (code "58") (name "unconnected-(IC11-HA-Pad1)") (class "Default")
      (node (ref "IC11") (pin "1") (pinfunction "HA_1") (pintype "bidirectional"))
    )
    (net (code "59") (name "unconnected-(IC11-HB-Pad4)") (class "Default")
      (node (ref "IC11") (pin "4") (pinfunction "HB_4") (pintype "bidirectional"))
    )
    (net (code "60") (name "unconnected-(IC13-N.C-Pad3)") (class "Default")
      (node (ref "IC13") (pin "3") (pinfunction "N.C_3") (pintype "no_connect"))
    )
  )
)
